# XBee-Explorer-DongleMini-v14.net
KiCad netlist of a schematic drawn in EAGLE
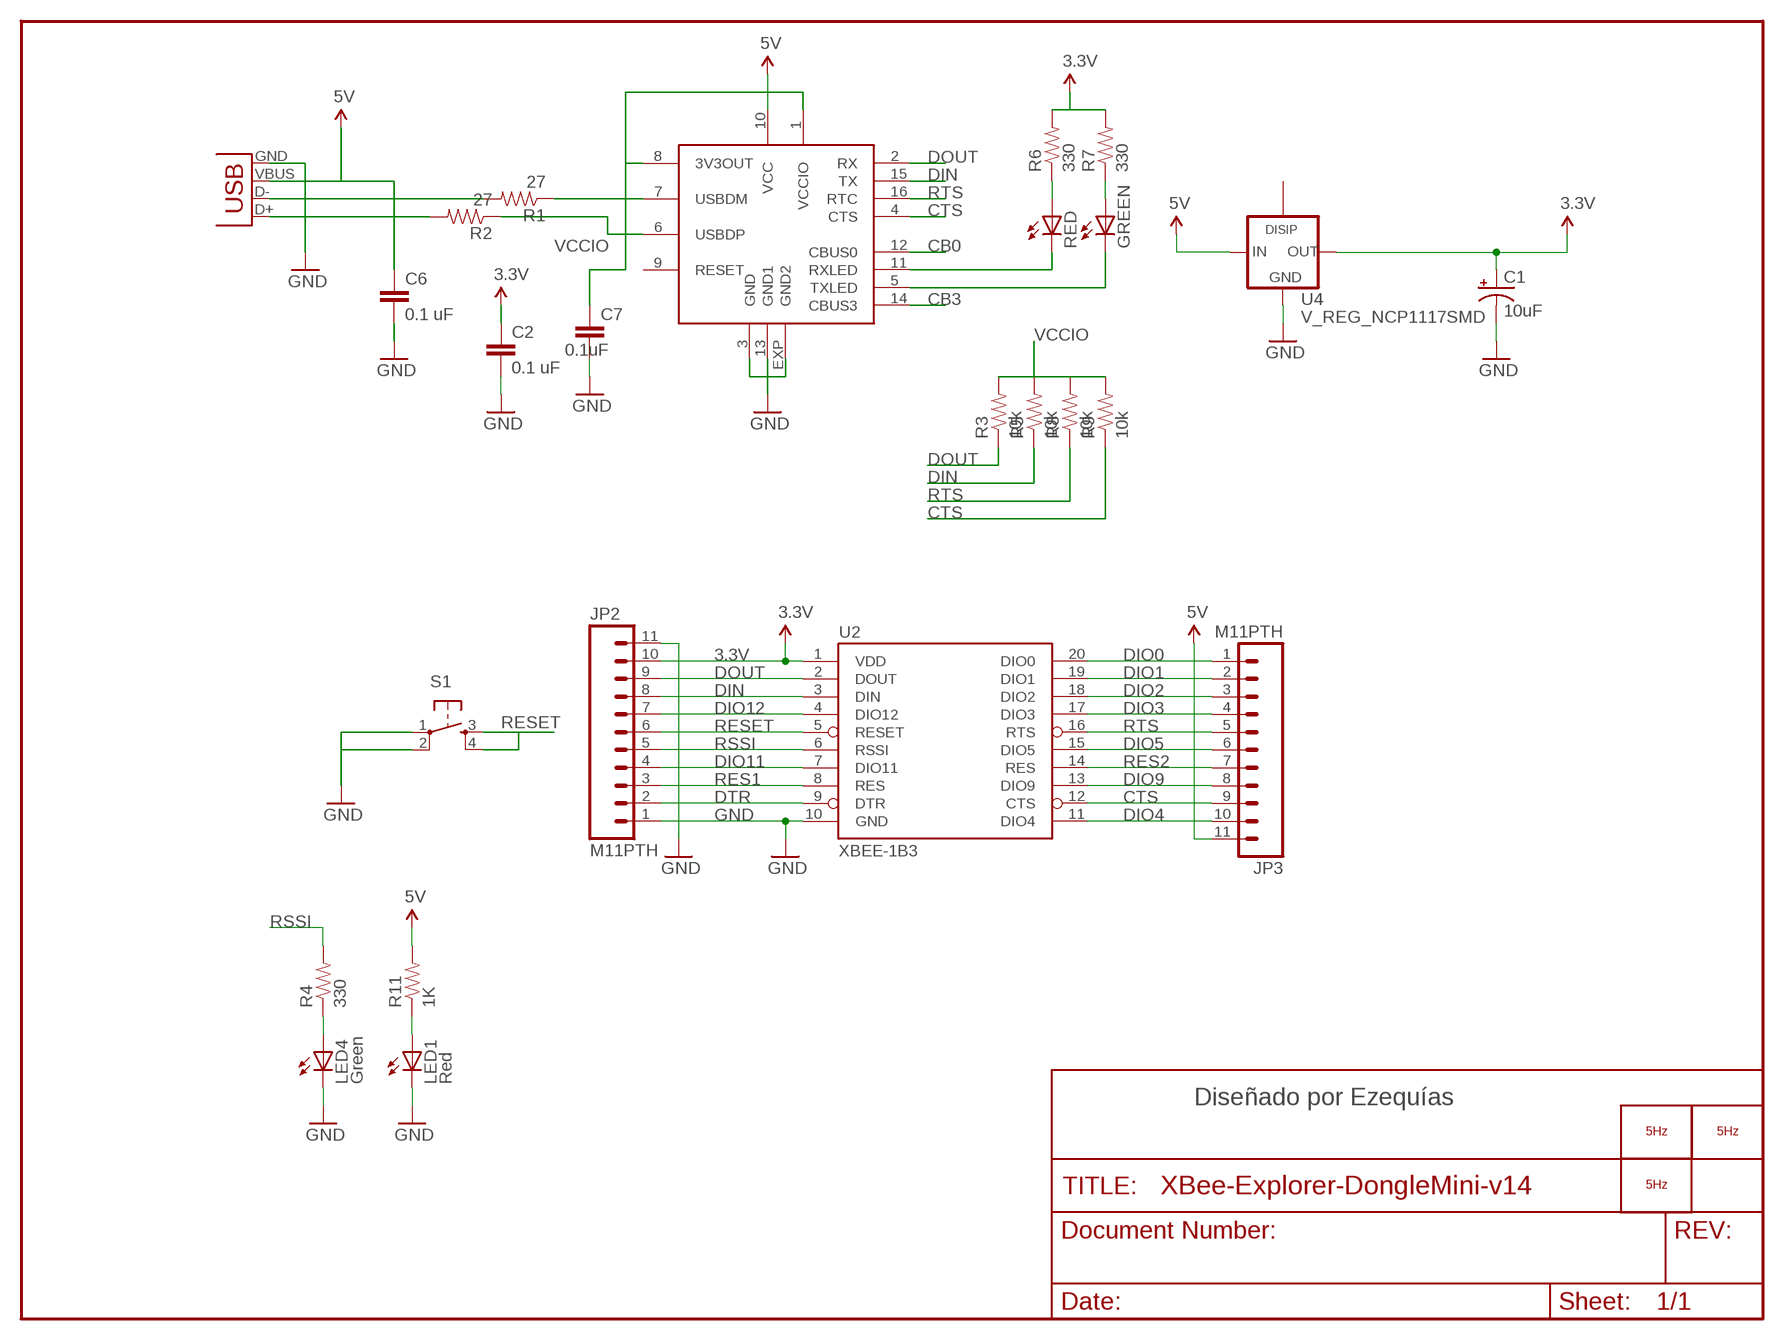
[diagram p0: schematic, sheet 1]

(export (version "E")
  (design (tool "Eeschema 10.0.6"))
  (components
    (comp (ref "C1")
      (value "10uF")
      (footprint "eagle-import:EIA3216")
      (libsource (lib "eagle-import") (part "CAP_POL1206"))
    )
    (comp (ref "C2")
      (value "0.1 uF")
      (footprint "eagle-import:0603-CAP")
      (libsource (lib "eagle-import") (part "CAP0603-CAP"))
    )
    (comp (ref "C6")
      (value "0.1 uF")
      (footprint "eagle-import:0603-CAP")
      (libsource (lib "eagle-import") (part "CAP0603-CAP"))
    )
    (comp (ref "C7")
      (value "0.1uF")
      (footprint "eagle-import:0603-CAP")
      (libsource (lib "eagle-import") (part "CAP0603-CAP"))
    )
    (comp (ref "GREEN")
      (value "LED0603")
      (footprint "eagle-import:LED-0603")
      (libsource (lib "eagle-import") (part "LED0603"))
    )
    (comp (ref "JP2")
      (value "M11PTH")
      (footprint "eagle-import:1X11")
      (libsource (lib "eagle-import") (part "M11PTH"))
    )
    (comp (ref "JP3")
      (value "M11PTH")
      (footprint "eagle-import:1X11")
      (libsource (lib "eagle-import") (part "M11PTH"))
    )
    (comp (ref "LED1")
      (value "Red")
      (footprint "eagle-import:LED-0603")
      (libsource (lib "eagle-import") (part "LED0603"))
    )
    (comp (ref "LED4")
      (value "Green")
      (footprint "eagle-import:LED-0603")
      (libsource (lib "eagle-import") (part "LED0603"))
    )
    (comp (ref "LOGO2")
      (value "LOGO_5HZ_H_10MM")
      (footprint "eagle-import:5HZ_LOGO_H_10MM")
      (libsource (lib "eagle-import") (part "LOGO_5HZ_H_10MM"))
    )
    (comp (ref "LOGO3")
      (value "LOGO_5HZ_H_COOPER_15MM")
      (footprint "eagle-import:5HZ_LOGO_H_COOPER_15MM")
      (libsource (lib "eagle-import") (part "LOGO_5HZ_H_COOPER_15MM"))
    )
    (comp (ref "LOGO4")
      (value "LOGO_5HZ_WEB_COOPER_10MM")
      (footprint "eagle-import:5HZ_WEB_COOPER_10MM")
      (libsource (lib "eagle-import") (part "LOGO_5HZ_WEB_COOPER_10MM"))
    )
    (comp (ref "R1")
      (value "27")
      (footprint "eagle-import:0603-RES")
      (libsource (lib "eagle-import") (part "RESISTOR0603-RES"))
    )
    (comp (ref "R2")
      (value "27")
      (footprint "eagle-import:0603-RES")
      (libsource (lib "eagle-import") (part "RESISTOR0603-RES"))
    )
    (comp (ref "R3")
      (value "10k")
      (footprint "eagle-import:0603-RES")
      (libsource (lib "eagle-import") (part "RESISTOR0603-RES"))
    )
    (comp (ref "R4")
      (value "330")
      (footprint "eagle-import:0603-RES")
      (libsource (lib "eagle-import") (part "RESISTOR0603-RES"))
    )
    (comp (ref "R5")
      (value "10k")
      (footprint "eagle-import:0603-RES")
      (libsource (lib "eagle-import") (part "RESISTOR0603-RES"))
    )
    (comp (ref "R6")
      (value "330")
      (footprint "eagle-import:0603-RES")
      (libsource (lib "eagle-import") (part "RESISTOR0603-RES"))
    )
    (comp (ref "R7")
      (value "330")
      (footprint "eagle-import:0603-RES")
      (libsource (lib "eagle-import") (part "RESISTOR0603-RES"))
    )
    (comp (ref "R8")
      (value "10k")
      (footprint "eagle-import:0603-RES")
      (libsource (lib "eagle-import") (part "RESISTOR0603-RES"))
    )
    (comp (ref "R9")
      (value "10k")
      (footprint "eagle-import:0603-RES")
      (libsource (lib "eagle-import") (part "RESISTOR0603-RES"))
    )
    (comp (ref "R11")
      (value "1K")
      (footprint "eagle-import:0603-RES")
      (libsource (lib "eagle-import") (part "RESISTOR0603-RES"))
    )
    (comp (ref "RED")
      (value "LED0603")
      (footprint "eagle-import:LED-0603")
      (libsource (lib "eagle-import") (part "LED0603"))
    )
    (comp (ref "S1")
      (value "TAC_SWITCHSMD")
      (footprint "eagle-import:TACTILE_SWITCH_SMD")
      (libsource (lib "eagle-import") (part "TAC_SWITCHSMD"))
    )
    (comp (ref "U$5")
      (value "FT230")
      (footprint "eagle-import:QFN-16")
      (libsource (lib "eagle-import") (part "FT230"))
    )
    (comp (ref "U2")
      (value "XBEE-1B3")
      (footprint "eagle-import:XBEE-SMD")
      (libsource (lib "eagle-import") (part "XBEE-1B3"))
    )
    (comp (ref "U4")
      (value "V_REG_NCP1117SMD")
      (footprint "eagle-import:SOT223")
      (libsource (lib "eagle-import") (part "V_REG_NCP1117SMD"))
    )
    (comp (ref "X1")
      (value "USBSMD")
      (footprint "eagle-import:USB-MINIB")
      (libsource (lib "eagle-import") (part "USBSMD"))
    )
  )
  (nets
    (net (code "1") (name "/CB0") (class "Default")
      (node (ref "U$5") (pin "12") (pinfunction "CBUS0_12") (pintype "bidirectional"))
    )
    (net (code "2") (name "/CB3") (class "Default")
      (node (ref "U$5") (pin "14") (pinfunction "CBUS3_14") (pintype "bidirectional"))
    )
    (net (code "3") (name "/CTS") (class "Default")
      (node (ref "JP3") (pin "9") (pinfunction "9_9") (pintype "passive"))
      (node (ref "R9") (pin "1") (pinfunction "1_1") (pintype "passive"))
      (node (ref "U$5") (pin "4") (pinfunction "CTS_4") (pintype "bidirectional"))
      (node (ref "U2") (pin "12") (pinfunction "CTS_12") (pintype "output"))
    )
    (net (code "4") (name "/DIN") (class "Default")
      (node (ref "JP2") (pin "8") (pinfunction "8_8") (pintype "passive"))
      (node (ref "R5") (pin "1") (pinfunction "1_1") (pintype "passive"))
      (node (ref "U$5") (pin "15") (pinfunction "TX_15") (pintype "bidirectional"))
      (node (ref "U2") (pin "3") (pinfunction "DIN_3") (pintype "input"))
    )
    (net (code "5") (name "/DIO0") (class "Default")
      (node (ref "JP3") (pin "1") (pinfunction "1_1") (pintype "passive"))
      (node (ref "U2") (pin "20") (pinfunction "DIO0_20") (pintype "bidirectional"))
    )
    (net (code "6") (name "/DIO1") (class "Default")
      (node (ref "JP3") (pin "2") (pinfunction "2_2") (pintype "passive"))
      (node (ref "U2") (pin "19") (pinfunction "DIO1_19") (pintype "bidirectional"))
    )
    (net (code "7") (name "/DIO2") (class "Default")
      (node (ref "JP3") (pin "3") (pinfunction "3_3") (pintype "passive"))
      (node (ref "U2") (pin "18") (pinfunction "DIO2_18") (pintype "bidirectional"))
    )
    (net (code "8") (name "/DIO3") (class "Default")
      (node (ref "JP3") (pin "4") (pinfunction "4_4") (pintype "passive"))
      (node (ref "U2") (pin "17") (pinfunction "DIO3_17") (pintype "bidirectional"))
    )
    (net (code "9") (name "/DIO4") (class "Default")
      (node (ref "JP3") (pin "10") (pinfunction "10_10") (pintype "passive"))
      (node (ref "U2") (pin "11") (pinfunction "DIO4_11") (pintype "bidirectional"))
    )
    (net (code "10") (name "/DIO5") (class "Default")
      (node (ref "JP3") (pin "6") (pinfunction "6_6") (pintype "passive"))
      (node (ref "U2") (pin "15") (pinfunction "DIO5_15") (pintype "bidirectional"))
    )
    (net (code "11") (name "/DIO9") (class "Default")
      (node (ref "JP3") (pin "8") (pinfunction "8_8") (pintype "passive"))
      (node (ref "U2") (pin "13") (pinfunction "DIO9_13") (pintype "bidirectional"))
    )
    (net (code "12") (name "/DIO11") (class "Default")
      (node (ref "JP2") (pin "4") (pinfunction "4_4") (pintype "passive"))
      (node (ref "U2") (pin "7") (pinfunction "DIO11_7") (pintype "bidirectional"))
    )
    (net (code "13") (name "/DIO12") (class "Default")
      (node (ref "JP2") (pin "7") (pinfunction "7_7") (pintype "passive"))
      (node (ref "U2") (pin "4") (pinfunction "DIO12_4") (pintype "bidirectional"))
    )
    (net (code "14") (name "/DOUT") (class "Default")
      (node (ref "JP2") (pin "9") (pinfunction "9_9") (pintype "passive"))
      (node (ref "R3") (pin "1") (pinfunction "1_1") (pintype "passive"))
      (node (ref "U$5") (pin "2") (pinfunction "RX_2") (pintype "bidirectional"))
      (node (ref "U2") (pin "2") (pinfunction "DOUT_2") (pintype "output"))
    )
    (net (code "15") (name "/DTR") (class "Default")
      (node (ref "JP2") (pin "2") (pinfunction "2_2") (pintype "passive"))
      (node (ref "U2") (pin "9") (pinfunction "DTR_9") (pintype "bidirectional"))
    )
    (net (code "16") (name "/RES1") (class "Default")
      (node (ref "JP2") (pin "3") (pinfunction "3_3") (pintype "passive"))
      (node (ref "U2") (pin "8") (pinfunction "RES_8") (pintype "bidirectional"))
    )
    (net (code "17") (name "/RES2") (class "Default")
      (node (ref "JP3") (pin "7") (pinfunction "7_7") (pintype "passive"))
      (node (ref "U2") (pin "14") (pinfunction "RES_14") (pintype "bidirectional"))
    )
    (net (code "18") (name "/RESET") (class "Default")
      (node (ref "JP2") (pin "6") (pinfunction "6_6") (pintype "passive"))
      (node (ref "S1") (pin "3") (pinfunction "3_3") (pintype "passive"))
      (node (ref "S1") (pin "4") (pinfunction "4_4") (pintype "passive"))
      (node (ref "U2") (pin "5") (pinfunction "RESET_5") (pintype "input"))
    )
    (net (code "19") (name "/RSSI") (class "Default")
      (node (ref "JP2") (pin "5") (pinfunction "5_5") (pintype "passive"))
      (node (ref "R4") (pin "2") (pinfunction "2_2") (pintype "passive"))
      (node (ref "U2") (pin "6") (pinfunction "RSSI_6") (pintype "bidirectional"))
    )
    (net (code "20") (name "/RTS") (class "Default")
      (node (ref "JP3") (pin "5") (pinfunction "5_5") (pintype "passive"))
      (node (ref "R8") (pin "1") (pinfunction "1_1") (pintype "passive"))
      (node (ref "U$5") (pin "16") (pinfunction "RTC_16") (pintype "bidirectional"))
      (node (ref "U2") (pin "16") (pinfunction "RTS_16") (pintype "input"))
    )
    (net (code "21") (name "/VCCIO") (class "Default")
      (node (ref "C7") (pin "1") (pinfunction "1_1") (pintype "passive"))
      (node (ref "R3") (pin "2") (pinfunction "2_2") (pintype "passive"))
      (node (ref "R5") (pin "2") (pinfunction "2_2") (pintype "passive"))
      (node (ref "R8") (pin "2") (pinfunction "2_2") (pintype "passive"))
      (node (ref "R9") (pin "2") (pinfunction "2_2") (pintype "passive"))
      (node (ref "U$5") (pin "1") (pinfunction "VCCIO_1") (pintype "bidirectional"))
      (node (ref "U$5") (pin "8") (pinfunction "3V3OUT_8") (pintype "bidirectional"))
    )
    (net (code "22") (name "3.3V") (class "Default")
      (node (ref "C1") (pin "A") (pinfunction "+_A") (pintype "passive"))
      (node (ref "C2") (pin "1") (pinfunction "1_1") (pintype "passive"))
      (node (ref "JP2") (pin "10") (pinfunction "10_10") (pintype "passive"))
      (node (ref "R6") (pin "2") (pinfunction "2_2") (pintype "passive"))
      (node (ref "R7") (pin "2") (pinfunction "2_2") (pintype "passive"))
      (node (ref "U2") (pin "1") (pinfunction "VDD_1") (pintype "power_in"))
      (node (ref "U4") (pin "2") (pinfunction "OUT_2") (pintype "output"))
    )
    (net (code "23") (name "5V") (class "Default")
      (node (ref "C6") (pin "1") (pinfunction "1_1") (pintype "passive"))
      (node (ref "JP3") (pin "11") (pinfunction "11_11") (pintype "passive"))
      (node (ref "R11") (pin "2") (pinfunction "2_2") (pintype "passive"))
      (node (ref "U$5") (pin "10") (pinfunction "VCC_10") (pintype "bidirectional"))
      (node (ref "U4") (pin "3") (pinfunction "IN_3") (pintype "input"))
      (node (ref "X1") (pin "VBUS") (pinfunction "VBUS_VBUS") (pintype "bidirectional"))
    )
    (net (code "24") (name "GND") (class "Default")
      (node (ref "C1") (pin "C") (pinfunction "-_C") (pintype "passive"))
      (node (ref "C2") (pin "2") (pinfunction "2_2") (pintype "passive"))
      (node (ref "C6") (pin "2") (pinfunction "2_2") (pintype "passive"))
      (node (ref "C7") (pin "2") (pinfunction "2_2") (pintype "passive"))
      (node (ref "JP2") (pin "1") (pinfunction "1_1") (pintype "passive"))
      (node (ref "JP2") (pin "11") (pinfunction "11_11") (pintype "passive"))
      (node (ref "LED1") (pin "C") (pinfunction "C_C") (pintype "passive"))
      (node (ref "LED4") (pin "C") (pinfunction "C_C") (pintype "passive"))
      (node (ref "S1") (pin "1") (pinfunction "1_1") (pintype "passive"))
      (node (ref "S1") (pin "2") (pinfunction "2_2") (pintype "passive"))
      (node (ref "U$5") (pin "13") (pinfunction "GND1_13") (pintype "bidirectional"))
      (node (ref "U$5") (pin "3") (pinfunction "GND_3") (pintype "bidirectional"))
      (node (ref "U$5") (pin "EXP") (pinfunction "GND2_EXP") (pintype "bidirectional"))
      (node (ref "U2") (pin "10") (pinfunction "GND_10") (pintype "power_in"))
      (node (ref "U4") (pin "1") (pinfunction "GND_1") (pintype "input"))
      (node (ref "X1") (pin "GND") (pinfunction "GND_GND") (pintype "bidirectional"))
    )
    (net (code "25") (name "Net-(GREEN-PadA)") (class "Default")
      (node (ref "GREEN") (pin "A") (pinfunction "A_A") (pintype "passive"))
      (node (ref "R7") (pin "1") (pinfunction "1_1") (pintype "passive"))
    )
    (net (code "26") (name "Net-(LED1-PadA)") (class "Default")
      (node (ref "LED1") (pin "A") (pinfunction "A_A") (pintype "passive"))
      (node (ref "R11") (pin "1") (pinfunction "1_1") (pintype "passive"))
    )
    (net (code "27") (name "Net-(LED4-PadA)") (class "Default")
      (node (ref "LED4") (pin "A") (pinfunction "A_A") (pintype "passive"))
      (node (ref "R4") (pin "1") (pinfunction "1_1") (pintype "passive"))
    )
    (net (code "28") (name "Net-(R1-Pad2)") (class "Default")
      (node (ref "R1") (pin "2") (pinfunction "2_2") (pintype "passive"))
      (node (ref "X1") (pin "D-") (pinfunction "D-_D-") (pintype "bidirectional"))
    )
    (net (code "29") (name "Net-(R2-Pad2)") (class "Default")
      (node (ref "R2") (pin "2") (pinfunction "2_2") (pintype "passive"))
      (node (ref "X1") (pin "D+") (pinfunction "D+_D+") (pintype "bidirectional"))
    )
    (net (code "30") (name "Net-(R6-Pad1)") (class "Default")
      (node (ref "R6") (pin "1") (pinfunction "1_1") (pintype "passive"))
      (node (ref "RED") (pin "A") (pinfunction "A_A") (pintype "passive"))
    )
    (net (code "31") (name "Net-(U$5-RXLED)") (class "Default")
      (node (ref "RED") (pin "C") (pinfunction "C_C") (pintype "passive"))
      (node (ref "U$5") (pin "11") (pinfunction "RXLED_11") (pintype "bidirectional"))
    )
    (net (code "32") (name "Net-(U$5-TXLED)") (class "Default")
      (node (ref "GREEN") (pin "C") (pinfunction "C_C") (pintype "passive"))
      (node (ref "U$5") (pin "5") (pinfunction "TXLED_5") (pintype "bidirectional"))
    )
    (net (code "33") (name "Net-(U$5-USBDM)") (class "Default")
      (node (ref "R1") (pin "1") (pinfunction "1_1") (pintype "passive"))
      (node (ref "U$5") (pin "7") (pinfunction "USBDM_7") (pintype "bidirectional"))
    )
    (net (code "34") (name "Net-(U$5-USBDP)") (class "Default")
      (node (ref "R2") (pin "1") (pinfunction "1_1") (pintype "passive"))
      (node (ref "U$5") (pin "6") (pinfunction "USBDP_6") (pintype "bidirectional"))
    )
    (net (code "35") (name "unconnected-(U$5-RESET-Pad9)") (class "Default")
      (node (ref "U$5") (pin "9") (pinfunction "RESET_9") (pintype "bidirectional"))
    )
    (net (code "36") (name "unconnected-(U4-P$1-Pad4)") (class "Default")
      (node (ref "U4") (pin "4") (pinfunction "P$1_4") (pintype "bidirectional"))
    )
  )
)
